# spb_sch1.net
KiCad netlist of a schematic drawn in Altium Designer
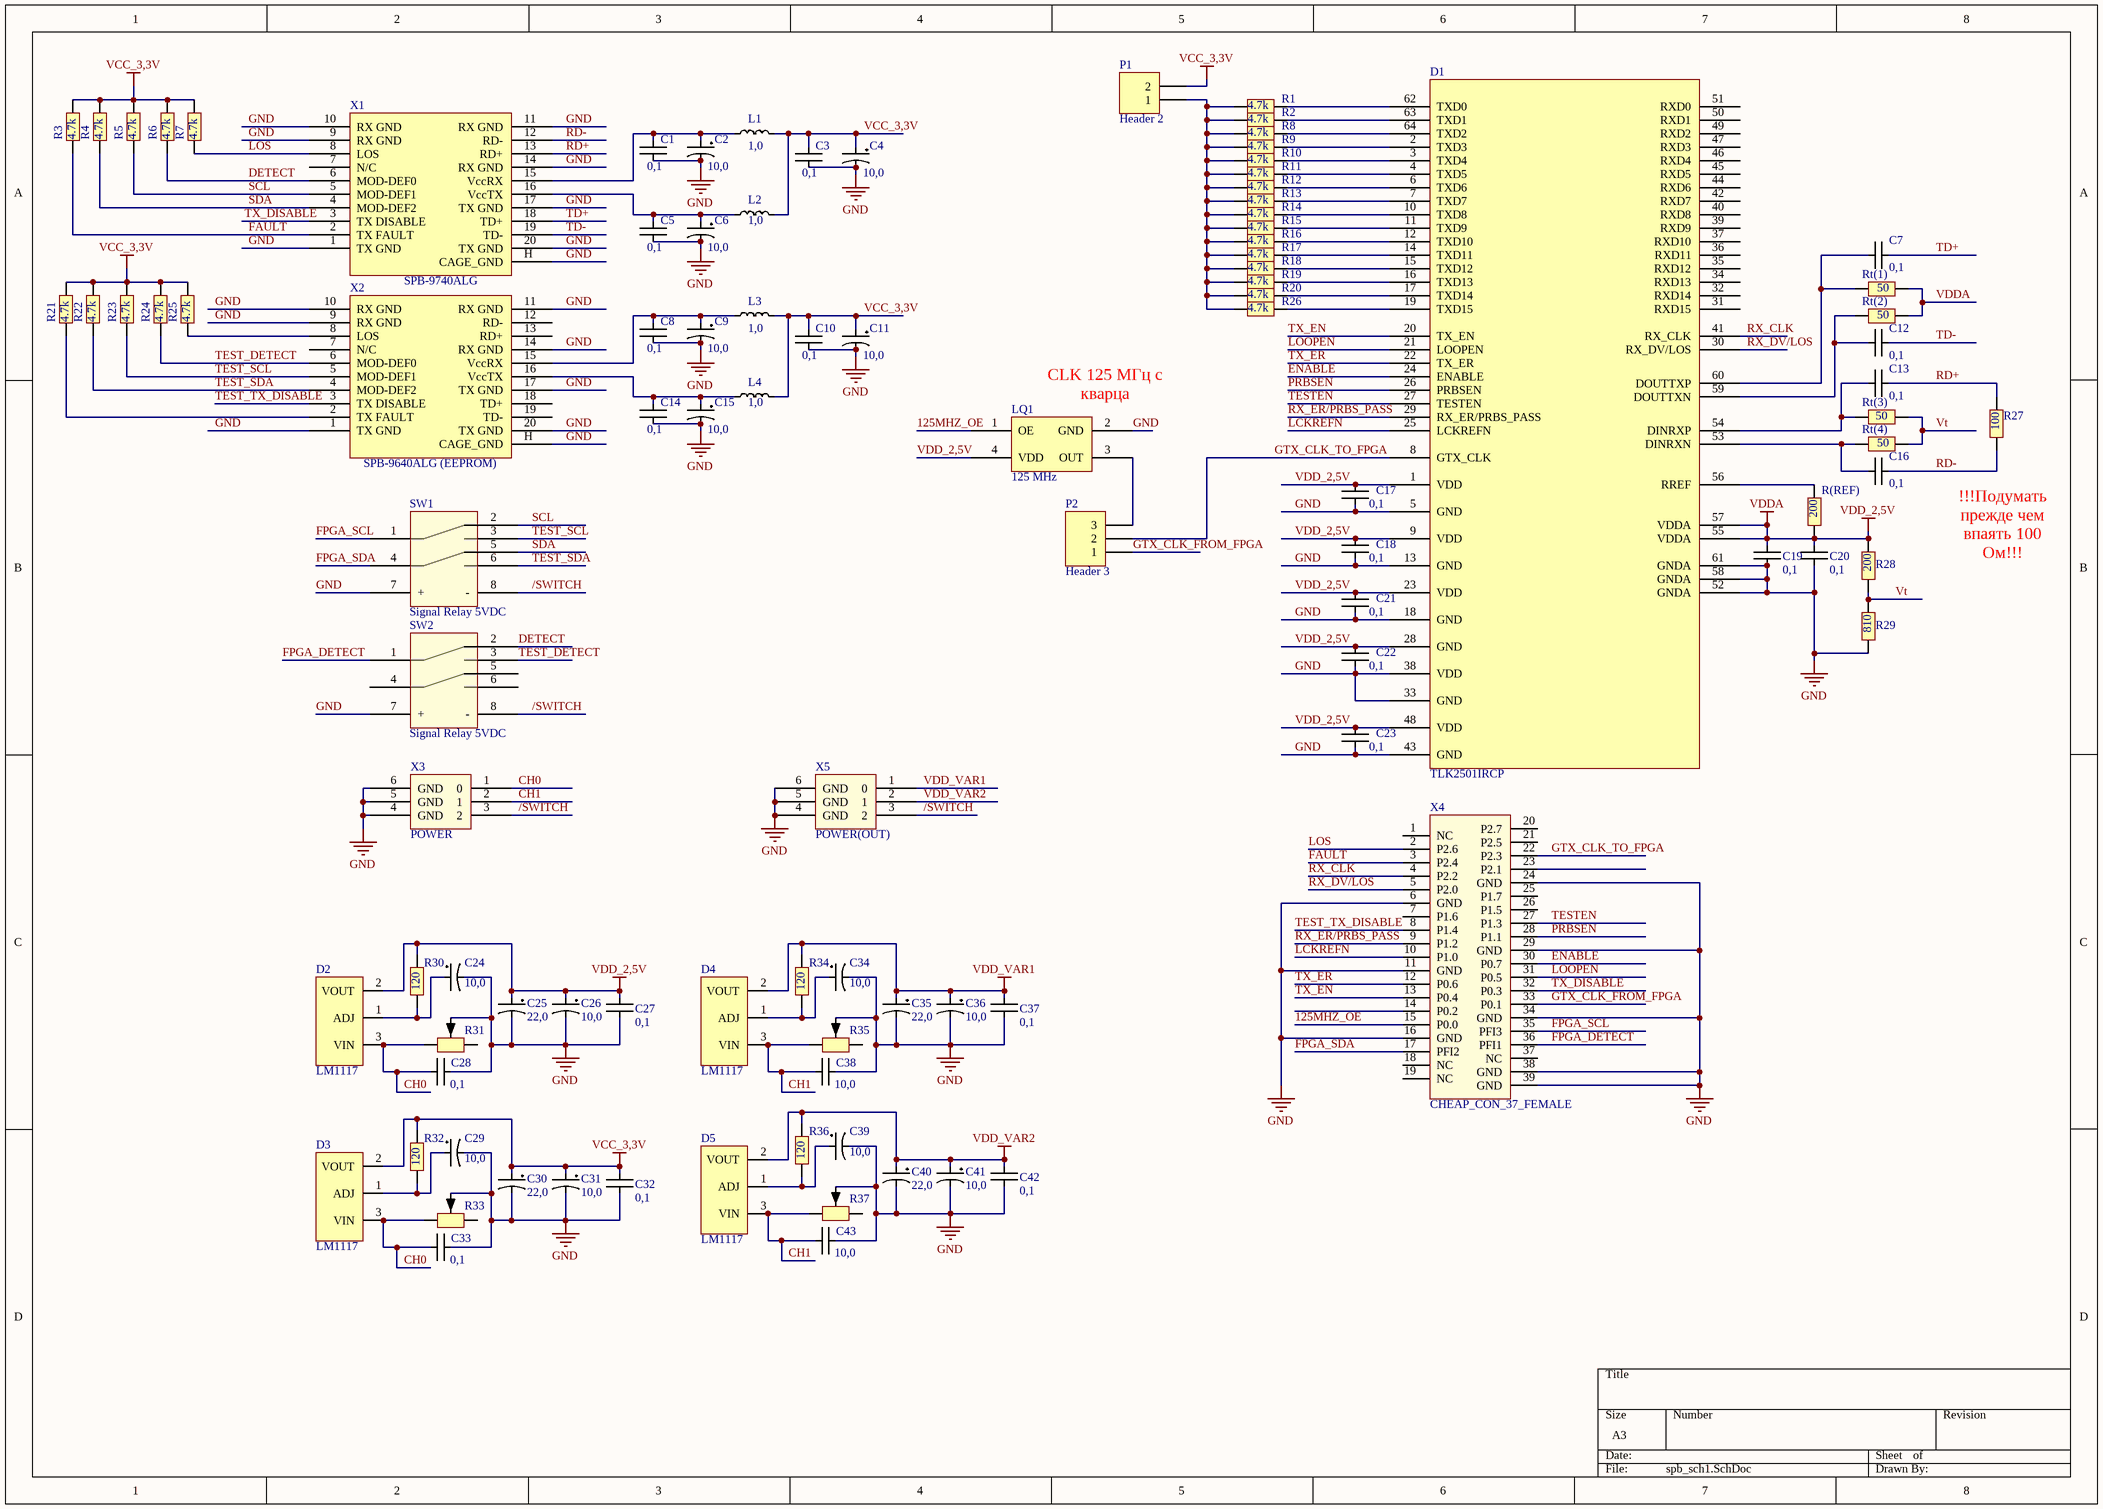
[diagram p0: spb_sch1.SchDoc]

(export (version "E")
  (design (tool "Eeschema 10.0.6"))
  (components
    (comp (ref "C1")
      (value "0,1")
      (footprint "0805")
      (description "0805")
      (libsource (lib "MIT_Schlib") (part "CAP_SMALL"))
    )
    (comp (ref "C2")
      (value "10,0")
      (footprint "TYPE_C")
      (description "SMD")
      (libsource (lib "MIT_Schlib") (part "CAP_TANT"))
    )
    (comp (ref "C3")
      (value "0,1")
      (footprint "0805")
      (description "0805")
      (libsource (lib "MIT_Schlib") (part "CAP_SMALL"))
    )
    (comp (ref "C4")
      (value "10,0")
      (footprint "TYPE_C")
      (description "SMD")
      (libsource (lib "MIT_Schlib") (part "CAP_TANT"))
    )
    (comp (ref "C5")
      (value "0,1")
      (footprint "0805")
      (description "0805")
      (libsource (lib "MIT_Schlib") (part "CAP_SMALL"))
    )
    (comp (ref "C6")
      (value "10,0")
      (footprint "TYPE_C")
      (description "SMD")
      (libsource (lib "MIT_Schlib") (part "CAP_TANT"))
    )
    (comp (ref "C7")
      (value "0,1")
      (footprint "0805")
      (description "0805")
      (libsource (lib "MIT_Schlib") (part "CAP_SMALL"))
    )
    (comp (ref "C8")
      (value "0,1")
      (footprint "0805")
      (description "0805")
      (libsource (lib "MIT_Schlib") (part "CAP_SMALL"))
    )
    (comp (ref "C9")
      (value "10,0")
      (footprint "TYPE_C")
      (description "SMD")
      (libsource (lib "MIT_Schlib") (part "CAP_TANT"))
    )
    (comp (ref "C10")
      (value "0,1")
      (footprint "0805")
      (description "0805")
      (libsource (lib "MIT_Schlib") (part "CAP_SMALL"))
    )
    (comp (ref "C11")
      (value "10,0")
      (footprint "TYPE_C")
      (description "SMD")
      (libsource (lib "MIT_Schlib") (part "CAP_TANT"))
    )
    (comp (ref "C12")
      (value "0,1")
      (footprint "0805")
      (description "0805")
      (libsource (lib "MIT_Schlib") (part "CAP_SMALL"))
    )
    (comp (ref "C13")
      (value "0,1")
      (footprint "0805")
      (description "0805")
      (libsource (lib "MIT_Schlib") (part "CAP_SMALL"))
    )
    (comp (ref "C14")
      (value "0,1")
      (footprint "0805")
      (description "0805")
      (libsource (lib "MIT_Schlib") (part "CAP_SMALL"))
    )
    (comp (ref "C15")
      (value "10,0")
      (footprint "TYPE_C")
      (description "SMD")
      (libsource (lib "MIT_Schlib") (part "CAP_TANT"))
    )
    (comp (ref "C16")
      (value "0,1")
      (footprint "0805")
      (description "0805")
      (libsource (lib "MIT_Schlib") (part "CAP_SMALL"))
    )
    (comp (ref "C17")
      (value "0,1")
      (footprint "0805")
      (description "0805")
      (libsource (lib "MIT_Schlib") (part "CAP_SMALL"))
    )
    (comp (ref "C18")
      (value "0,1")
      (footprint "0805")
      (description "0805")
      (libsource (lib "MIT_Schlib") (part "CAP_SMALL"))
    )
    (comp (ref "C19")
      (value "0,1")
      (footprint "0805")
      (description "0805")
      (libsource (lib "MIT_Schlib") (part "CAP_SMALL"))
    )
    (comp (ref "C20")
      (value "0,1")
      (footprint "0805")
      (description "0805")
      (libsource (lib "MIT_Schlib") (part "CAP_SMALL"))
    )
    (comp (ref "C21")
      (value "0,1")
      (footprint "0805")
      (description "0805")
      (libsource (lib "MIT_Schlib") (part "CAP_SMALL"))
    )
    (comp (ref "C22")
      (value "0,1")
      (footprint "0805")
      (description "0805")
      (libsource (lib "MIT_Schlib") (part "CAP_SMALL"))
    )
    (comp (ref "C23")
      (value "0,1")
      (footprint "0805")
      (description "0805")
      (libsource (lib "MIT_Schlib") (part "CAP_SMALL"))
    )
    (comp (ref "C24")
      (value "10,0")
      (footprint "TYPE_C")
      (description "SMD")
      (libsource (lib "MIT_Schlib") (part "CAP_TANT"))
    )
    (comp (ref "C25")
      (value "22,0")
      (footprint "TYPE_C")
      (description "SMD")
      (libsource (lib "MIT_Schlib") (part "CAP_TANT"))
    )
    (comp (ref "C26")
      (value "10,0")
      (footprint "TYPE_C")
      (description "SMD")
      (libsource (lib "MIT_Schlib") (part "CAP_TANT"))
    )
    (comp (ref "C27")
      (value "0,1")
      (footprint "0805")
      (description "0805")
      (libsource (lib "MIT_Schlib") (part "CAP_SMALL"))
    )
    (comp (ref "C28")
      (value "0,1")
      (footprint "0805")
      (description "0805")
      (libsource (lib "MIT_Schlib") (part "CAP_SMALL"))
    )
    (comp (ref "C29")
      (value "10,0")
      (footprint "TYPE_C")
      (description "SMD")
      (libsource (lib "MIT_Schlib") (part "CAP_TANT"))
    )
    (comp (ref "C30")
      (value "22,0")
      (footprint "TYPE_C")
      (description "SMD")
      (libsource (lib "MIT_Schlib") (part "CAP_TANT"))
    )
    (comp (ref "C31")
      (value "10,0")
      (footprint "TYPE_C")
      (description "SMD")
      (libsource (lib "MIT_Schlib") (part "CAP_TANT"))
    )
    (comp (ref "C32")
      (value "0,1")
      (footprint "0805")
      (description "0805")
      (libsource (lib "MIT_Schlib") (part "CAP_SMALL"))
    )
    (comp (ref "C33")
      (value "0,1")
      (footprint "0805")
      (description "0805")
      (libsource (lib "MIT_Schlib") (part "CAP_SMALL"))
    )
    (comp (ref "C34")
      (value "10,0")
      (footprint "TYPE_C")
      (description "SMD")
      (libsource (lib "MIT_Schlib") (part "CAP_TANT"))
    )
    (comp (ref "C35")
      (value "22,0")
      (footprint "TYPE_C")
      (description "SMD")
      (libsource (lib "MIT_Schlib") (part "CAP_TANT"))
    )
    (comp (ref "C36")
      (value "10,0")
      (footprint "TYPE_C")
      (description "SMD")
      (libsource (lib "MIT_Schlib") (part "CAP_TANT"))
    )
    (comp (ref "C37")
      (value "0,1")
      (footprint "0805")
      (description "0805")
      (libsource (lib "MIT_Schlib") (part "CAP_SMALL"))
    )
    (comp (ref "C38")
      (value "10,0")
      (footprint "0805")
      (description "0805")
      (libsource (lib "MIT_Schlib") (part "CAP_SMALL"))
    )
    (comp (ref "C39")
      (value "10,0")
      (footprint "TYPE_C")
      (description "SMD")
      (libsource (lib "MIT_Schlib") (part "CAP_TANT"))
    )
    (comp (ref "C40")
      (value "22,0")
      (footprint "TYPE_C")
      (description "SMD")
      (libsource (lib "MIT_Schlib") (part "CAP_TANT"))
    )
    (comp (ref "C41")
      (value "10,0")
      (footprint "TYPE_C")
      (description "SMD")
      (libsource (lib "MIT_Schlib") (part "CAP_TANT"))
    )
    (comp (ref "C42")
      (value "0,1")
      (footprint "0805")
      (description "0805")
      (libsource (lib "MIT_Schlib") (part "CAP_SMALL"))
    )
    (comp (ref "C43")
      (value "10,0")
      (footprint "0805")
      (description "0805")
      (libsource (lib "MIT_Schlib") (part "CAP_SMALL"))
    )
    (comp (ref "D1")
      (value "TLK2501IRCP")
      (footprint "Quad64")
      (libsource (lib "MIT_Schlib") (part "TLK2501IRCP"))
    )
    (comp (ref "D2") (value "LM1117") (footprint "TO-252") (libsource (lib "MIT_Schlib") (part "LM1117_ADJ")))
    (comp (ref "D3") (value "LM1117") (footprint "TO-252") (libsource (lib "MIT_Schlib") (part "LM1117_ADJ")))
    (comp (ref "D4") (value "LM1117") (footprint "TO-252") (libsource (lib "MIT_Schlib") (part "LM1117_ADJ")))
    (comp (ref "D5") (value "LM1117") (footprint "TO-252") (libsource (lib "MIT_Schlib") (part "LM1117_ADJ")))
    (comp (ref "L1")
      (value "1,0")
      (footprint "0805")
      (description "0805")
      (libsource (lib "MIT_Schlib") (part "INDUCT"))
    )
    (comp (ref "L2")
      (value "1,0")
      (footprint "0805")
      (description "0805")
      (libsource (lib "MIT_Schlib") (part "INDUCT"))
    )
    (comp (ref "L3")
      (value "1,0")
      (footprint "0805")
      (description "0805")
      (libsource (lib "MIT_Schlib") (part "INDUCT"))
    )
    (comp (ref "L4")
      (value "1,0")
      (footprint "0805")
      (description "0805")
      (libsource (lib "MIT_Schlib") (part "INDUCT"))
    )
    (comp (ref "LQ1")
      (value "125 MHz")
      (footprint "SOC7 SMD Clock Oscillator")
      (libsource (lib "MIT_Schlib") (part "SOC7 SMD Clock Oscillator"))
    )
    (comp (ref "P1")
      (value "Header 2")
      (footprint "HDR1X2")
      (description "Header, 2-Pin")
      (fields (field (name "PUBLISHER") "Altium Limited"))
      (libsource (lib "Miscellaneous Connectors") (part "Header 2"))
    )
    (comp (ref "P2")
      (value "Header 3")
      (footprint "HDR1X3")
      (description "Header, 3-Pin")
      (fields (field (name "PUBLISHER") "Altium Limited"))
      (libsource (lib "Miscellaneous Connectors") (part "Header 3"))
    )
    (comp (ref "R(REF)")
      (value "200")
      (footprint "0805")
      (description "0805")
      (libsource (lib "") (part "RES0805_2"))
    )
    (comp (ref "R1")
      (value "4.7k")
      (footprint "0805")
      (description "0805")
      (libsource (lib "") (part "RES0805_1"))
    )
    (comp (ref "R2")
      (value "4.7k")
      (footprint "0805")
      (description "0805")
      (libsource (lib "") (part "RES0805_1"))
    )
    (comp (ref "R3")
      (value "4.7k")
      (footprint "0805")
      (description "0805")
      (libsource (lib "") (part "RES0805_3"))
    )
    (comp (ref "R4")
      (value "4.7k")
      (footprint "0805")
      (description "0805")
      (libsource (lib "") (part "RES0805_3"))
    )
    (comp (ref "R5")
      (value "4.7k")
      (footprint "0805")
      (description "0805")
      (libsource (lib "") (part "RES0805_3"))
    )
    (comp (ref "R6")
      (value "4.7k")
      (footprint "0805")
      (description "0805")
      (libsource (lib "") (part "RES0805_3"))
    )
    (comp (ref "R7")
      (value "4.7k")
      (footprint "0805")
      (description "0805")
      (libsource (lib "") (part "RES0805_3"))
    )
    (comp (ref "R8")
      (value "4.7k")
      (footprint "0805")
      (description "0805")
      (libsource (lib "") (part "RES0805_1"))
    )
    (comp (ref "R9")
      (value "4.7k")
      (footprint "0805")
      (description "0805")
      (libsource (lib "") (part "RES0805_1"))
    )
    (comp (ref "R10")
      (value "4.7k")
      (footprint "0805")
      (description "0805")
      (libsource (lib "") (part "RES0805_1"))
    )
    (comp (ref "R11")
      (value "4.7k")
      (footprint "0805")
      (description "0805")
      (libsource (lib "") (part "RES0805_1"))
    )
    (comp (ref "R12")
      (value "4.7k")
      (footprint "0805")
      (description "0805")
      (libsource (lib "") (part "RES0805_1"))
    )
    (comp (ref "R13")
      (value "4.7k")
      (footprint "0805")
      (description "0805")
      (libsource (lib "") (part "RES0805_1"))
    )
    (comp (ref "R14")
      (value "4.7k")
      (footprint "0805")
      (description "0805")
      (libsource (lib "") (part "RES0805_1"))
    )
    (comp (ref "R15")
      (value "4.7k")
      (footprint "0805")
      (description "0805")
      (libsource (lib "") (part "RES0805_1"))
    )
    (comp (ref "R16")
      (value "4.7k")
      (footprint "0805")
      (description "0805")
      (libsource (lib "") (part "RES0805_1"))
    )
    (comp (ref "R17")
      (value "4.7k")
      (footprint "0805")
      (description "0805")
      (libsource (lib "") (part "RES0805_1"))
    )
    (comp (ref "R18")
      (value "4.7k")
      (footprint "0805")
      (description "0805")
      (libsource (lib "") (part "RES0805_1"))
    )
    (comp (ref "R19")
      (value "4.7k")
      (footprint "0805")
      (description "0805")
      (libsource (lib "") (part "RES0805_1"))
    )
    (comp (ref "R20")
      (value "4.7k")
      (footprint "0805")
      (description "0805")
      (libsource (lib "") (part "RES0805_1"))
    )
    (comp (ref "R21")
      (value "4.7k")
      (footprint "0805")
      (description "0805")
      (libsource (lib "") (part "RES0805_3"))
    )
    (comp (ref "R22")
      (value "4.7k")
      (footprint "0805")
      (description "0805")
      (libsource (lib "") (part "RES0805_3"))
    )
    (comp (ref "R23")
      (value "4.7k")
      (footprint "0805")
      (description "0805")
      (libsource (lib "") (part "RES0805_3"))
    )
    (comp (ref "R24")
      (value "4.7k")
      (footprint "0805")
      (description "0805")
      (libsource (lib "") (part "RES0805_3"))
    )
    (comp (ref "R25")
      (value "4.7k")
      (footprint "0805")
      (description "0805")
      (libsource (lib "") (part "RES0805_3"))
    )
    (comp (ref "R26")
      (value "4.7k")
      (footprint "0805")
      (description "0805")
      (libsource (lib "") (part "RES0805_1"))
    )
    (comp (ref "R27")
      (value "100")
      (footprint "0805")
      (description "0805")
      (libsource (lib "") (part "RES0805_3"))
    )
    (comp (ref "R28")
      (value "200")
      (footprint "0805")
      (description "0805")
      (libsource (lib "") (part "RES0805_2"))
    )
    (comp (ref "R29")
      (value "810")
      (footprint "0805")
      (description "0805")
      (libsource (lib "") (part "RES0805_2"))
    )
    (comp (ref "R30")
      (value "120")
      (footprint "0805")
      (description "0805")
      (libsource (lib "") (part "RES0805_3"))
    )
    (comp (ref "R31")
      (value "RES_VAR")
      (footprint "3006P")
      (description "PV36W102C (СП5-2ВБ) 1 кОм")
      (libsource (lib "MIT_Schlib") (part "RES_VAR"))
    )
    (comp (ref "R32") (value "120") (footprint "0805") (libsource (lib "") (part "RES0805_3")))
    (comp (ref "R33")
      (value "RES_VAR")
      (footprint "3006P")
      (description "PV36W102C (СП5-2ВБ) 1 кОм")
      (libsource (lib "MIT_Schlib") (part "RES_VAR"))
    )
    (comp (ref "R34")
      (value "120")
      (footprint "0805")
      (description "0805")
      (libsource (lib "") (part "RES0805_3"))
    )
    (comp (ref "R35")
      (value "RES_VAR")
      (footprint "3006P")
      (description "PV36W102C (СП5-2ВБ) 1 кОм")
      (libsource (lib "MIT_Schlib") (part "RES_VAR"))
    )
    (comp (ref "R36")
      (value "120")
      (footprint "0805")
      (description "0805")
      (libsource (lib "") (part "RES0805_3"))
    )
    (comp (ref "R37")
      (value "RES_VAR")
      (footprint "3006P")
      (description "PV36W102C (СП5-2ВБ) 1 кОм")
      (libsource (lib "MIT_Schlib") (part "RES_VAR"))
    )
    (comp (ref "Rt(1)")
      (value "50")
      (footprint "0805")
      (description "0805")
      (libsource (lib "MIT_Schlib") (part "RES0805"))
    )
    (comp (ref "Rt(2)")
      (value "50")
      (footprint "0805")
      (description "0805")
      (libsource (lib "MIT_Schlib") (part "RES0805"))
    )
    (comp (ref "Rt(3)")
      (value "50")
      (footprint "0805")
      (description "0805")
      (libsource (lib "MIT_Schlib") (part "RES0805"))
    )
    (comp (ref "Rt(4)")
      (value "50")
      (footprint "0805")
      (description "0805")
      (libsource (lib "MIT_Schlib") (part "RES0805"))
    )
    (comp (ref "SW1")
      (value "Signal Relay 5VDC")
      (footprint "V23079 Relay")
      (libsource (lib "MIT_Schlib") (part "SWITCH"))
    )
    (comp (ref "SW2")
      (value "Signal Relay 5VDC")
      (footprint "V23079 Relay")
      (libsource (lib "MIT_Schlib") (part "SWITCH"))
    )
    (comp (ref "X1")
      (value "SPB-9740ALG")
      (footprint "SFP-20pin")
      (libsource (lib "MIT_Schlib") (part "SFP-20pin"))
    )
    (comp (ref "X2")
      (value "SPB-9640ALG (EEPROM)")
      (footprint "SFP-20pin")
      (libsource (lib "MIT_Schlib") (part "SFP-20pin"))
    )
    (comp (ref "X3") (value "POWER") (footprint "POWER") (libsource (lib "Schlib") (part "POWER")))
    (comp (ref "X4")
      (value "CHEAP_CON_37_FEMALE")
      (footprint "CHEAP_CONN_FEMALE")
      (libsource (lib "Schlib") (part "CHEAP_CON_37_FEMALE"))
    )
    (comp (ref "X5") (value "POWER(OUT)") (footprint "POWER") (libsource (lib "Schlib") (part "POWER")))
  )
  (nets
    (net (code "1") (name "/125MHZ_OE") (class "Default")
      (node (ref "LQ1") (pin "1") (pinfunction "OE_1") (pintype "passive"))
      (node (ref "X4") (pin "15") (pinfunction "P0.0_15") (pintype "passive"))
    )
    (net (code "3") (name "/CH0") (class "Default")
      (node (ref "C28") (pin "1") (pinfunction "1_1") (pintype "passive"))
      (node (ref "C33") (pin "1") (pinfunction "1_1") (pintype "passive"))
      (node (ref "D2") (pin "3") (pinfunction "VIN_3") (pintype "passive"))
      (node (ref "D3") (pin "3") (pinfunction "VIN_3") (pintype "passive"))
      (node (ref "R31") (pin "3") (pinfunction "3_3") (pintype "passive"))
      (node (ref "R33") (pin "3") (pinfunction "3_3") (pintype "passive"))
      (node (ref "X3") (pin "1") (pinfunction "0_1") (pintype "passive"))
    )
    (net (code "4") (name "/CH1") (class "Default")
      (node (ref "C38") (pin "1") (pinfunction "1_1") (pintype "passive"))
      (node (ref "C43") (pin "1") (pinfunction "1_1") (pintype "passive"))
      (node (ref "D4") (pin "3") (pinfunction "VIN_3") (pintype "passive"))
      (node (ref "D5") (pin "3") (pinfunction "VIN_3") (pintype "passive"))
      (node (ref "R35") (pin "3") (pinfunction "3_3") (pintype "passive"))
      (node (ref "R37") (pin "3") (pinfunction "3_3") (pintype "passive"))
      (node (ref "X3") (pin "2") (pinfunction "1_2") (pintype "passive"))
    )
    (net (code "5") (name "/DETECT") (class "Default")
      (node (ref "R6") (pin "2") (pinfunction "2_2") (pintype "passive"))
      (node (ref "SW2") (pin "2") (pinfunction "-_2") (pintype "passive"))
      (node (ref "X1") (pin "6") (pinfunction "MOD-DEF0_6") (pintype "passive"))
    )
    (net (code "6") (name "/ENABLE") (class "Default")
      (node (ref "D1") (pin "24") (pinfunction "ENABLE_24") (pintype "passive"))
      (node (ref "X4") (pin "30") (pinfunction "P0.7_30") (pintype "passive"))
    )
    (net (code "7") (name "/FAULT") (class "Default")
      (node (ref "R3") (pin "2") (pinfunction "2_2") (pintype "passive"))
      (node (ref "X1") (pin "2") (pinfunction "TX_FAULT_2") (pintype "passive"))
      (node (ref "X4") (pin "3") (pinfunction "P2.4_3") (pintype "passive"))
    )
    (net (code "8") (name "/FPGA_DETECT") (class "Default")
      (node (ref "SW2") (pin "1") (pinfunction "-_1") (pintype "passive"))
      (node (ref "X4") (pin "36") (pinfunction "PFI1_36") (pintype "passive"))
    )
    (net (code "9") (name "/FPGA_SCL") (class "Default")
      (node (ref "SW1") (pin "1") (pinfunction "-_1") (pintype "passive"))
      (node (ref "X4") (pin "35") (pinfunction "PFI3_35") (pintype "passive"))
    )
    (net (code "10") (name "/FPGA_SDA") (class "Default")
      (node (ref "SW1") (pin "4") (pinfunction "-_4") (pintype "passive"))
      (node (ref "X4") (pin "17") (pinfunction "PFI2_17") (pintype "passive"))
    )
    (net (code "11") (name "/GTX_CLK_FROM_FPGA") (class "Default")
      (node (ref "P2") (pin "1") (pinfunction "1_1") (pintype "passive"))
      (node (ref "X4") (pin "33") (pinfunction "P0.1_33") (pintype "passive"))
    )
    (net (code "12") (name "/GTX_CLK_TO_FPGA") (class "Default")
      (node (ref "D1") (pin "8") (pinfunction "GTX_CLK_8") (pintype "passive"))
      (node (ref "P2") (pin "2") (pinfunction "2_2") (pintype "passive"))
      (node (ref "X4") (pin "22") (pinfunction "P2.3_22") (pintype "passive"))
    )
    (net (code "13") (name "/LCKREFN") (class "Default")
      (node (ref "D1") (pin "25") (pinfunction "LCKREFN_25") (pintype "passive"))
      (node (ref "X4") (pin "10") (pinfunction "P1.0_10") (pintype "passive"))
    )
    (net (code "14") (name "/LOOPEN") (class "Default")
      (node (ref "D1") (pin "21") (pinfunction "LOOPEN_21") (pintype "passive"))
      (node (ref "X4") (pin "31") (pinfunction "P0.5_31") (pintype "passive"))
    )
    (net (code "15") (name "/LOS") (class "Default")
      (node (ref "R7") (pin "2") (pinfunction "2_2") (pintype "passive"))
      (node (ref "X1") (pin "8") (pinfunction "LOS_8") (pintype "passive"))
      (node (ref "X4") (pin "2") (pinfunction "P2.6_2") (pintype "passive"))
    )
    (net (code "16") (name "/PRBSEN") (class "Default")
      (node (ref "D1") (pin "26") (pinfunction "PRBSEN_26") (pintype "passive"))
      (node (ref "X4") (pin "28") (pinfunction "P1.1_28") (pintype "passive"))
    )
    (net (code "17") (name "/RD+") (class "Default")
      (node (ref "C13") (pin "1") (pinfunction "1_1") (pintype "passive"))
      (node (ref "R27") (pin "1") (pinfunction "1_1") (pintype "passive"))
      (node (ref "X1") (pin "13") (pinfunction "RD+_13") (pintype "passive"))
    )
    (net (code "18") (name "/RD-") (class "Default")
      (node (ref "C16") (pin "1") (pinfunction "1_1") (pintype "passive"))
      (node (ref "R27") (pin "2") (pinfunction "2_2") (pintype "passive"))
      (node (ref "X1") (pin "12") (pinfunction "RD-_12") (pintype "passive"))
    )
    (net (code "19") (name "/RX_CLK") (class "Default")
      (node (ref "D1") (pin "41") (pinfunction "RX_CLK_41") (pintype "passive"))
      (node (ref "X4") (pin "4") (pinfunction "P2.2_4") (pintype "passive"))
    )
    (net (code "20") (name "/RX_DV{slash}LOS") (class "Default")
      (node (ref "D1") (pin "30") (pinfunction "RX_DV/LOS_30") (pintype "passive"))
      (node (ref "X4") (pin "5") (pinfunction "P2.0_5") (pintype "passive"))
    )
    (net (code "21") (name "/RX_ER{slash}PRBS_PASS") (class "Default")
      (node (ref "D1") (pin "29") (pinfunction "RX_ER/PRBS_PASS_29") (pintype "passive"))
      (node (ref "X4") (pin "9") (pinfunction "P1.2_9") (pintype "passive"))
    )
    (net (code "22") (name "/SCL") (class "Default")
      (node (ref "R5") (pin "2") (pinfunction "2_2") (pintype "passive"))
      (node (ref "SW1") (pin "2") (pinfunction "-_2") (pintype "passive"))
      (node (ref "X1") (pin "5") (pinfunction "MOD-DEF1_5") (pintype "passive"))
    )
    (net (code "23") (name "/SDA") (class "Default")
      (node (ref "R4") (pin "2") (pinfunction "2_2") (pintype "passive"))
      (node (ref "SW1") (pin "5") (pinfunction "-_5") (pintype "passive"))
      (node (ref "X1") (pin "4") (pinfunction "MOD-DEF2_4") (pintype "passive"))
    )
    (net (code "24") (name "/TD+") (class "Default")
      (node (ref "C7") (pin "1") (pinfunction "1_1") (pintype "passive"))
      (node (ref "X1") (pin "18") (pinfunction "TD+_18") (pintype "passive"))
    )
    (net (code "25") (name "/TD-") (class "Default")
      (node (ref "C12") (pin "1") (pinfunction "1_1") (pintype "passive"))
      (node (ref "X1") (pin "19") (pinfunction "TD-_19") (pintype "passive"))
    )
    (net (code "26") (name "/TESTEN") (class "Default")
      (node (ref "D1") (pin "27") (pinfunction "TESTEN_27") (pintype "passive"))
      (node (ref "X4") (pin "27") (pinfunction "P1.3_27") (pintype "passive"))
    )
    (net (code "27") (name "/TEST_DETECT") (class "Default")
      (node (ref "R24") (pin "2") (pinfunction "2_2") (pintype "passive"))
      (node (ref "SW2") (pin "3") (pinfunction "-_3") (pintype "passive"))
      (node (ref "X2") (pin "6") (pinfunction "MOD-DEF0_6") (pintype "passive"))
    )
    (net (code "28") (name "/TEST_SCL") (class "Default")
      (node (ref "R23") (pin "2") (pinfunction "2_2") (pintype "passive"))
      (node (ref "SW1") (pin "3") (pinfunction "-_3") (pintype "passive"))
      (node (ref "X2") (pin "5") (pinfunction "MOD-DEF1_5") (pintype "passive"))
    )
    (net (code "29") (name "/TEST_SDA") (class "Default")
      (node (ref "R22") (pin "2") (pinfunction "2_2") (pintype "passive"))
      (node (ref "SW1") (pin "6") (pinfunction "-_6") (pintype "passive"))
      (node (ref "X2") (pin "4") (pinfunction "MOD-DEF2_4") (pintype "passive"))
    )
    (net (code "30") (name "/TEST_TX_DISABLE") (class "Default")
      (node (ref "X2") (pin "3") (pinfunction "TX_DISABLE_3") (pintype "passive"))
      (node (ref "X4") (pin "8") (pinfunction "P1.4_8") (pintype "passive"))
    )
    (net (code "31") (name "/TX_DISABLE") (class "Default")
      (node (ref "X1") (pin "3") (pinfunction "TX_DISABLE_3") (pintype "passive"))
      (node (ref "X4") (pin "32") (pinfunction "P0.3_32") (pintype "passive"))
    )
    (net (code "32") (name "/TX_EN") (class "Default")
      (node (ref "D1") (pin "20") (pinfunction "TX_EN_20") (pintype "passive"))
      (node (ref "X4") (pin "13") (pinfunction "P0.4_13") (pintype "passive"))
    )
    (net (code "33") (name "/TX_ER") (class "Default")
      (node (ref "D1") (pin "22") (pinfunction "TX_ER_22") (pintype "passive"))
      (node (ref "X4") (pin "12") (pinfunction "P0.6_12") (pintype "passive"))
    )
    (net (code "34") (name "/Vt") (class "Default")
      (node (ref "R28") (pin "1") (pinfunction "1_1") (pintype "passive"))
      (node (ref "R29") (pin "2") (pinfunction "2_2") (pintype "passive"))
      (node (ref "Rt(3)") (pin "1") (pinfunction "1_1") (pintype "passive"))
      (node (ref "Rt(4)") (pin "1") (pinfunction "1_1") (pintype "passive"))
    )
    (net (code "35") (name "/{slash}SWITCH") (class "Default")
      (node (ref "SW1") (pin "8") (pinfunction "-_8") (pintype "passive"))
      (node (ref "SW2") (pin "8") (pinfunction "-_8") (pintype "passive"))
      (node (ref "X3") (pin "3") (pinfunction "2_3") (pintype "passive"))
      (node (ref "X5") (pin "3") (pinfunction "2_3") (pintype "passive"))
    )
    (net (code "36") (name "GND") (class "Default")
      (node (ref "C1") (pin "2") (pinfunction "2_2") (pintype "passive"))
      (node (ref "C10") (pin "2") (pinfunction "2_2") (pintype "passive"))
      (node (ref "C11") (pin "1") (pinfunction "1_1") (pintype "passive"))
      (node (ref "C14") (pin "2") (pinfunction "2_2") (pintype "passive"))
      (node (ref "C15") (pin "1") (pinfunction "1_1") (pintype "passive"))
      (node (ref "C17") (pin "2") (pinfunction "2_2") (pintype "passive"))
      (node (ref "C18") (pin "2") (pinfunction "2_2") (pintype "passive"))
      (node (ref "C19") (pin "1") (pinfunction "1_1") (pintype "passive"))
      (node (ref "C2") (pin "1") (pinfunction "1_1") (pintype "passive"))
      (node (ref "C20") (pin "1") (pinfunction "1_1") (pintype "passive"))
      (node (ref "C21") (pin "2") (pinfunction "2_2") (pintype "passive"))
      (node (ref "C22") (pin "2") (pinfunction "2_2") (pintype "passive"))
      (node (ref "C23") (pin "2") (pinfunction "2_2") (pintype "passive"))
      (node (ref "C24") (pin "1") (pinfunction "1_1") (pintype "passive"))
      (node (ref "C25") (pin "1") (pinfunction "1_1") (pintype "passive"))
      (node (ref "C26") (pin "1") (pinfunction "1_1") (pintype "passive"))
      (node (ref "C27") (pin "1") (pinfunction "1_1") (pintype "passive"))
      (node (ref "C28") (pin "2") (pinfunction "2_2") (pintype "passive"))
      (node (ref "C29") (pin "1") (pinfunction "1_1") (pintype "passive"))
      (node (ref "C3") (pin "2") (pinfunction "2_2") (pintype "passive"))
      (node (ref "C30") (pin "1") (pinfunction "1_1") (pintype "passive"))
      (node (ref "C31") (pin "1") (pinfunction "1_1") (pintype "passive"))
      (node (ref "C32") (pin "1") (pinfunction "1_1") (pintype "passive"))
      (node (ref "C33") (pin "2") (pinfunction "2_2") (pintype "passive"))
      (node (ref "C34") (pin "1") (pinfunction "1_1") (pintype "passive"))
      (node (ref "C35") (pin "1") (pinfunction "1_1") (pintype "passive"))
      (node (ref "C36") (pin "1") (pinfunction "1_1") (pintype "passive"))
      (node (ref "C37") (pin "1") (pinfunction "1_1") (pintype "passive"))
      (node (ref "C38") (pin "2") (pinfunction "2_2") (pintype "passive"))
      (node (ref "C39") (pin "1") (pinfunction "1_1") (pintype "passive"))
      (node (ref "C4") (pin "1") (pinfunction "1_1") (pintype "passive"))
      (node (ref "C40") (pin "1") (pinfunction "1_1") (pintype "passive"))
      (node (ref "C41") (pin "1") (pinfunction "1_1") (pintype "passive"))
      (node (ref "C42") (pin "1") (pinfunction "1_1") (pintype "passive"))
      (node (ref "C43") (pin "2") (pinfunction "2_2") (pintype "passive"))
      (node (ref "C5") (pin "2") (pinfunction "2_2") (pintype "passive"))
      (node (ref "C6") (pin "1") (pinfunction "1_1") (pintype "passive"))
      (node (ref "C8") (pin "2") (pinfunction "2_2") (pintype "passive"))
      (node (ref "C9") (pin "1") (pinfunction "1_1") (pintype "passive"))
      (node (ref "D1") (pin "13") (pinfunction "GND_13") (pintype "passive"))
      (node (ref "D1") (pin "18") (pinfunction "GND_18") (pintype "passive"))
      (node (ref "D1") (pin "33") (pinfunction "GND_33") (pintype "passive"))
      (node (ref "D1") (pin "38") (pinfunction "VDD_38") (pintype "passive"))
      (node (ref "D1") (pin "43") (pinfunction "GND_43") (pintype "passive"))
      (node (ref "D1") (pin "5") (pinfunction "GND_5") (pintype "passive"))
      (node (ref "D1") (pin "52") (pinfunction "GNDA_52") (pintype "passive"))
      (node (ref "D1") (pin "58") (pinfunction "GNDA_58") (pintype "passive"))
      (node (ref "D1") (pin "61") (pinfunction "GNDA_61") (pintype "passive"))
      (node (ref "LQ1") (pin "2") (pinfunction "GND_2") (pintype "passive"))
      (node (ref "R29") (pin "1") (pinfunction "1_1") (pintype "passive"))
      (node (ref "R31") (pin "2") (pinfunction "2_2") (pintype "passive"))
      (node (ref "R33") (pin "2") (pinfunction "2_2") (pintype "passive"))
      (node (ref "R35") (pin "2") (pinfunction "2_2") (pintype "passive"))
      (node (ref "R37") (pin "2") (pinfunction "2_2") (pintype "passive"))
      (node (ref "SW1") (pin "7") (pinfunction "+_7") (pintype "passive"))
      (node (ref "SW2") (pin "7") (pinfunction "+_7") (pintype "passive"))
      (node (ref "X1") (pin "1") (pinfunction "TX_GND_1") (pintype "passive"))
      (node (ref "X1") (pin "10") (pinfunction "RX_GND_10") (pintype "passive"))
      (node (ref "X1") (pin "11") (pinfunction "RX_GND_11") (pintype "passive"))
      (node (ref "X1") (pin "14") (pinfunction "RX_GND_14") (pintype "passive"))
      (node (ref "X1") (pin "17") (pinfunction "TX_GND_17") (pintype "passive"))
      (node (ref "X1") (pin "20") (pinfunction "TX_GND_20") (pintype "passive"))
      (node (ref "X1") (pin "9") (pinfunction "RX_GND_9") (pintype "passive"))
      (node (ref "X1") (pin "H") (pinfunction "CAGE_GND_H") (pintype "passive"))
      (node (ref "X2") (pin "1") (pinfunction "TX_GND_1") (pintype "passive"))
      (node (ref "X2") (pin "10") (pinfunction "RX_GND_10") (pintype "passive"))
      (node (ref "X2") (pin "11") (pinfunction "RX_GND_11") (pintype "passive"))
      (node (ref "X2") (pin "14") (pinfunction "RX_GND_14") (pintype "passive"))
      (node (ref "X2") (pin "17") (pinfunction "TX_GND_17") (pintype "passive"))
      (node (ref "X2") (pin "20") (pinfunction "TX_GND_20") (pintype "passive"))
      (node (ref "X2") (pin "9") (pinfunction "RX_GND_9") (pintype "passive"))
      (node (ref "X2") (pin "H") (pinfunction "CAGE_GND_H") (pintype "passive"))
      (node (ref "X3") (pin "4") (pinfunction "GND_4") (pintype "passive"))
      (node (ref "X3") (pin "5") (pinfunction "GND_5") (pintype "passive"))
      (node (ref "X3") (pin "6") (pinfunction "GND_6") (pintype "passive"))
      (node (ref "X4") (pin "11") (pinfunction "GND_11") (pintype "passive"))
      (node (ref "X4") (pin "16") (pinfunction "GND_16") (pintype "passive"))
      (node (ref "X4") (pin "24") (pinfunction "GND_24") (pintype "passive"))
      (node (ref "X4") (pin "29") (pinfunction "GND_29") (pintype "passive"))
      (node (ref "X4") (pin "34") (pinfunction "GND_34") (pintype "passive"))
      (node (ref "X4") (pin "38") (pinfunction "GND_38") (pintype "passive"))
      (node (ref "X4") (pin "39") (pinfunction "GND_39") (pintype "passive"))
      (node (ref "X4") (pin "6") (pinfunction "GND_6") (pintype "passive"))
      (node (ref "X5") (pin "4") (pinfunction "GND_4") (pintype "passive"))
      (node (ref "X5") (pin "5") (pinfunction "GND_5") (pintype "passive"))
      (node (ref "X5") (pin "6") (pinfunction "GND_6") (pintype "passive"))
    )
    (net (code "37") (name "Net-(D1-DINRXN)") (class "Default")
      (node (ref "C16") (pin "2") (pinfunction "2_2") (pintype "passive"))
      (node (ref "D1") (pin "53") (pinfunction "DINRXN_53") (pintype "passive"))
      (node (ref "Rt(4)") (pin "2") (pinfunction "2_2") (pintype "passive"))
    )
    (net (code "38") (name "Net-(D1-DINRXP)") (class "Default")
      (node (ref "C13") (pin "2") (pinfunction "2_2") (pintype "passive"))
      (node (ref "D1") (pin "54") (pinfunction "DINRXP_54") (pintype "passive"))
      (node (ref "Rt(3)") (pin "2") (pinfunction "2_2") (pintype "passive"))
    )
    (net (code "39") (name "Net-(D1-DOUTTXN)") (class "Default")
      (node (ref "C12") (pin "2") (pinfunction "2_2") (pintype "passive"))
      (node (ref "D1") (pin "59") (pinfunction "DOUTTXN_59") (pintype "passive"))
      (node (ref "Rt(2)") (pin "2") (pinfunction "2_2") (pintype "passive"))
    )
    (net (code "40") (name "Net-(D1-DOUTTXP)") (class "Default")
      (node (ref "C7") (pin "2") (pinfunction "2_2") (pintype "passive"))
      (node (ref "D1") (pin "60") (pinfunction "DOUTTXP_60") (pintype "passive"))
      (node (ref "Rt(1)") (pin "2") (pinfunction "2_2") (pintype "passive"))
    )
    (net (code "41") (name "Net-(D1-RREF)") (class "Default")
      (node (ref "D1") (pin "56") (pinfunction "RREF_56") (pintype "passive"))
      (node (ref "R(REF)") (pin "2") (pinfunction "2_2") (pintype "passive"))
    )
    (net (code "42") (name "Net-(D1-TXD0)") (class "Default")
      (node (ref "D1") (pin "62") (pinfunction "TXD0_62") (pintype "passive"))
      (node (ref "R1") (pin "2") (pinfunction "2_2") (pintype "passive"))
    )
    (net (code "43") (name "Net-(D1-TXD1)") (class "Default")
      (node (ref "D1") (pin "63") (pinfunction "TXD1_63") (pintype "passive"))
      (node (ref "R2") (pin "2") (pinfunction "2_2") (pintype "passive"))
    )
    (net (code "44") (name "Net-(D1-TXD2)") (class "Default")
      (node (ref "D1") (pin "64") (pinfunction "TXD2_64") (pintype "passive"))
      (node (ref "R8") (pin "2") (pinfunction "2_2") (pintype "passive"))
    )
    (net (code "45") (name "Net-(D1-TXD3)") (class "Default")
      (node (ref "D1") (pin "2") (pinfunction "TXD3_2") (pintype "passive"))
      (node (ref "R9") (pin "2") (pinfunction "2_2") (pintype "passive"))
    )
    (net (code "46") (name "Net-(D1-TXD4)") (class "Default")
      (node (ref "D1") (pin "3") (pinfunction "TXD4_3") (pintype "passive"))
      (node (ref "R10") (pin "2") (pinfunction "2_2") (pintype "passive"))
    )
    (net (code "47") (name "Net-(D1-TXD5)") (class "Default")
      (node (ref "D1") (pin "4") (pinfunction "TXD5_4") (pintype "passive"))
      (node (ref "R11") (pin "2") (pinfunction "2_2") (pintype "passive"))
    )
    (net (code "48") (name "Net-(D1-TXD6)") (class "Default")
      (node (ref "D1") (pin "6") (pinfunction "TXD6_6") (pintype "passive"))
      (node (ref "R12") (pin "2") (pinfunction "2_2") (pintype "passive"))
    )
    (net (code "49") (name "Net-(D1-TXD7)") (class "Default")
      (node (ref "D1") (pin "7") (pinfunction "TXD7_7") (pintype "passive"))
      (node (ref "R13") (pin "2") (pinfunction "2_2") (pintype "passive"))
    )
    (net (code "50") (name "Net-(D1-TXD8)") (class "Default")
      (node (ref "D1") (pin "10") (pinfunction "TXD8_10") (pintype "passive"))
      (node (ref "R14") (pin "2") (pinfunction "2_2") (pintype "passive"))
    )
    (net (code "51") (name "Net-(D1-TXD9)") (class "Default")
      (node (ref "D1") (pin "11") (pinfunction "TXD9_11") (pintype "passive"))
      (node (ref "R15") (pin "2") (pinfunction "2_2") (pintype "passive"))
    )
    (net (code "52") (name "Net-(D1-TXD10)") (class "Default")
      (node (ref "D1") (pin "12") (pinfunction "TXD10_12") (pintype "passive"))
      (node (ref "R16") (pin "2") (pinfunction "2_2") (pintype "passive"))
    )
    (net (code "53") (name "Net-(D1-TXD11)") (class "Default")
      (node (ref "D1") (pin "14") (pinfunction "TXD11_14") (pintype "passive"))
      (node (ref "R17") (pin "2") (pinfunction "2_2") (pintype "passive"))
    )
    (net (code "54") (name "Net-(D1-TXD12)") (class "Default")
      (node (ref "D1") (pin "15") (pinfunction "TXD12_15") (pintype "passive"))
      (node (ref "R18") (pin "2") (pinfunction "2_2") (pintype "passive"))
    )
    (net (code "55") (name "Net-(D1-TXD13)") (class "Default")
      (node (ref "D1") (pin "16") (pinfunction "TXD13_16") (pintype "passive"))
      (node (ref "R19") (pin "2") (pinfunction "2_2") (pintype "passive"))
    )
    (net (code "56") (name "Net-(D1-TXD14)") (class "Default")
      (node (ref "D1") (pin "17") (pinfunction "TXD14_17") (pintype "passive"))
      (node (ref "R20") (pin "2") (pinfunction "2_2") (pintype "passive"))
    )
    (net (code "57") (name "Net-(D1-TXD15)") (class "Default")
      (node (ref "D1") (pin "19") (pinfunction "TXD15_19") (pintype "passive"))
      (node (ref "R26") (pin "2") (pinfunction "2_2") (pintype "passive"))
    )
    (net (code "58") (name "Net-(D2-ADJ)") (class "Default")
      (node (ref "C24") (pin "2") (pinfunction "2_2") (pintype "passive"))
      (node (ref "D2") (pin "1") (pinfunction "ADJ_1") (pintype "passive"))
      (node (ref "R30") (pin "2") (pinfunction "2_2") (pintype "passive"))
    )
    (net (code "59") (name "Net-(D3-ADJ)") (class "Default")
      (node (ref "C29") (pin "2") (pinfunction "2_2") (pintype "passive"))
      (node (ref "D3") (pin "1") (pinfunction "ADJ_1") (pintype "passive"))
      (node (ref "R32") (pin "2") (pinfunction "2_2") (pintype "passive"))
    )
    (net (code "60") (name "Net-(D4-ADJ)") (class "Default")
      (node (ref "C34") (pin "2") (pinfunction "2_2") (pintype "passive"))
      (node (ref "D4") (pin "1") (pinfunction "ADJ_1") (pintype "passive"))
      (node (ref "R34") (pin "2") (pinfunction "2_2") (pintype "passive"))
    )
    (net (code "61") (name "Net-(D5-ADJ)") (class "Default")
      (node (ref "C39") (pin "2") (pinfunction "2_2") (pintype "passive"))
      (node (ref "D5") (pin "1") (pinfunction "ADJ_1") (pintype "passive"))
      (node (ref "R36") (pin "2") (pinfunction "2_2") (pintype "passive"))
    )
    (net (code "62") (name "Net-(LQ1-OUT)") (class "Default")
      (node (ref "LQ1") (pin "3") (pinfunction "OUT_3") (pintype "passive"))
      (node (ref "P2") (pin "3") (pinfunction "3_3") (pintype "passive"))
    )
    (net (code "63") (name "Net-(P1-Pad1)") (class "Default")
      (node (ref "P1") (pin "1") (pinfunction "1_1") (pintype "passive"))
      (node (ref "R1") (pin "1") (pinfunction "1_1") (pintype "passive"))
      (node (ref "R10") (pin "1") (pinfunction "1_1") (pintype "passive"))
      (node (ref "R11") (pin "1") (pinfunction "1_1") (pintype "passive"))
      (node (ref "R12") (pin "1") (pinfunction "1_1") (pintype "passive"))
      (node (ref "R13") (pin "1") (pinfunction "1_1") (pintype "passive"))
      (node (ref "R14") (pin "1") (pinfunction "1_1") (pintype "passive"))
      (node (ref "R15") (pin "1") (pinfunction "1_1") (pintype "passive"))
      (node (ref "R16") (pin "1") (pinfunction "1_1") (pintype "passive"))
      (node (ref "R17") (pin "1") (pinfunction "1_1") (pintype "passive"))
      (node (ref "R18") (pin "1") (pinfunction "1_1") (pintype "passive"))
      (node (ref "R19") (pin "1") (pinfunction "1_1") (pintype "passive"))
      (node (ref "R2") (pin "1") (pinfunction "1_1") (pintype "passive"))
      (node (ref "R20") (pin "1") (pinfunction "1_1") (pintype "passive"))
      (node (ref "R26") (pin "1") (pinfunction "1_1") (pintype "passive"))
      (node (ref "R8") (pin "1") (pinfunction "1_1") (pintype "passive"))
      (node (ref "R9") (pin "1") (pinfunction "1_1") (pintype "passive"))
    )
    (net (code "64") (name "Net-(X1-VccRX)") (class "Default")
      (node (ref "C1") (pin "1") (pinfunction "1_1") (pintype "passive"))
      (node (ref "C2") (pin "2") (pinfunction "2_2") (pintype "passive"))
      (node (ref "L1") (pin "1") (pinfunction "1_1") (pintype "passive"))
      (node (ref "X1") (pin "15") (pinfunction "VccRX_15") (pintype "passive"))
    )
    (net (code "65") (name "Net-(X1-VccTX)") (class "Default")
      (node (ref "C5") (pin "1") (pinfunction "1_1") (pintype "passive"))
      (node (ref "C6") (pin "2") (pinfunction "2_2") (pintype "passive"))
      (node (ref "L2") (pin "1") (pinfunction "1_1") (pintype "passive"))
      (node (ref "X1") (pin "16") (pinfunction "VccTX_16") (pintype "passive"))
    )
    (net (code "66") (name "Net-(X2-LOS)") (class "Default")
      (node (ref "R25") (pin "2") (pinfunction "2_2") (pintype "passive"))
      (node (ref "X2") (pin "8") (pinfunction "LOS_8") (pintype "passive"))
    )
    (net (code "67") (name "Net-(X2-TX_FAULT)") (class "Default")
      (node (ref "R21") (pin "2") (pinfunction "2_2") (pintype "passive"))
      (node (ref "X2") (pin "2") (pinfunction "TX_FAULT_2") (pintype "passive"))
    )
    (net (code "68") (name "Net-(X2-VccRX)") (class "Default")
      (node (ref "C8") (pin "1") (pinfunction "1_1") (pintype "passive"))
      (node (ref "C9") (pin "2") (pinfunction "2_2") (pintype "passive"))
      (node (ref "L3") (pin "1") (pinfunction "1_1") (pintype "passive"))
      (node (ref "X2") (pin "15") (pinfunction "VccRX_15") (pintype "passive"))
    )
    (net (code "69") (name "Net-(X2-VccTX)") (class "Default")
      (node (ref "C14") (pin "1") (pinfunction "1_1") (pintype "passive"))
      (node (ref "C15") (pin "2") (pinfunction "2_2") (pintype "passive"))
      (node (ref "L4") (pin "1") (pinfunction "1_1") (pintype "passive"))
      (node (ref "X2") (pin "16") (pinfunction "VccTX_16") (pintype "passive"))
    )
    (net (code "70") (name "VCC_3,3V") (class "Default")
      (node (ref "C10") (pin "1") (pinfunction "1_1") (pintype "passive"))
      (node (ref "C11") (pin "2") (pinfunction "2_2") (pintype "passive"))
      (node (ref "C3") (pin "1") (pinfunction "1_1") (pintype "passive"))
      (node (ref "C30") (pin "2") (pinfunction "2_2") (pintype "passive"))
      (node (ref "C31") (pin "2") (pinfunction "2_2") (pintype "passive"))
      (node (ref "C32") (pin "2") (pinfunction "2_2") (pintype "passive"))
      (node (ref "C4") (pin "2") (pinfunction "2_2") (pintype "passive"))
      (node (ref "D3") (pin "2") (pinfunction "VOUT_2") (pintype "passive"))
      (node (ref "L1") (pin "2") (pinfunction "2_2") (pintype "passive"))
      (node (ref "L2") (pin "2") (pinfunction "2_2") (pintype "passive"))
      (node (ref "L3") (pin "2") (pinfunction "2_2") (pintype "passive"))
      (node (ref "L4") (pin "2") (pinfunction "2_2") (pintype "passive"))
      (node (ref "P1") (pin "2") (pinfunction "2_2") (pintype "passive"))
      (node (ref "R21") (pin "1") (pinfunction "1_1") (pintype "passive"))
      (node (ref "R22") (pin "1") (pinfunction "1_1") (pintype "passive"))
      (node (ref "R23") (pin "1") (pinfunction "1_1") (pintype "passive"))
      (node (ref "R24") (pin "1") (pinfunction "1_1") (pintype "passive"))
      (node (ref "R25") (pin "1") (pinfunction "1_1") (pintype "passive"))
      (node (ref "R3") (pin "1") (pinfunction "1_1") (pintype "passive"))
      (node (ref "R32") (pin "1") (pinfunction "1_1") (pintype "passive"))
      (node (ref "R4") (pin "1") (pinfunction "1_1") (pintype "passive"))
      (node (ref "R5") (pin "1") (pinfunction "1_1") (pintype "passive"))
      (node (ref "R6") (pin "1") (pinfunction "1_1") (pintype "passive"))
      (node (ref "R7") (pin "1") (pinfunction "1_1") (pintype "passive"))
    )
    (net (code "71") (name "VDDA") (class "Default")
      (node (ref "C17") (pin "1") (pinfunction "1_1") (pintype "passive"))
      (node (ref "C18") (pin "1") (pinfunction "1_1") (pintype "passive"))
      (node (ref "C19") (pin "2") (pinfunction "2_2") (pintype "passive"))
      (node (ref "C20") (pin "2") (pinfunction "2_2") (pintype "passive"))
      (node (ref "C21") (pin "1") (pinfunction "1_1") (pintype "passive"))
      (node (ref "C22") (pin "1") (pinfunction "1_1") (pintype "passive"))
      (node (ref "C23") (pin "1") (pinfunction "1_1") (pintype "passive"))
      (node (ref "C25") (pin "2") (pinfunction "2_2") (pintype "passive"))
      (node (ref "C26") (pin "2") (pinfunction "2_2") (pintype "passive"))
      (node (ref "C27") (pin "2") (pinfunction "2_2") (pintype "passive"))
      (node (ref "D1") (pin "1") (pinfunction "VDD_1") (pintype "passive"))
      (node (ref "D1") (pin "23") (pinfunction "VDD_23") (pintype "passive"))
      (node (ref "D1") (pin "28") (pinfunction "GND_28") (pintype "passive"))
      (node (ref "D1") (pin "48") (pinfunction "VDD_48") (pintype "passive"))
      (node (ref "D1") (pin "55") (pinfunction "VDDA_55") (pintype "passive"))
      (node (ref "D1") (pin "57") (pinfunction "VDDA_57") (pintype "passive"))
      (node (ref "D1") (pin "9") (pinfunction "VDD_9") (pintype "passive"))
      (node (ref "D2") (pin "2") (pinfunction "VOUT_2") (pintype "passive"))
      (node (ref "LQ1") (pin "4") (pinfunction "VDD_4") (pintype "passive"))
      (node (ref "R(REF)") (pin "1") (pinfunction "1_1") (pintype "passive"))
      (node (ref "R28") (pin "2") (pinfunction "2_2") (pintype "passive"))
      (node (ref "R30") (pin "1") (pinfunction "1_1") (pintype "passive"))
      (node (ref "Rt(1)") (pin "1") (pinfunction "1_1") (pintype "passive"))
      (node (ref "Rt(2)") (pin "1") (pinfunction "1_1") (pintype "passive"))
    )
    (net (code "72") (name "VDD_VAR1") (class "Default")
      (node (ref "C35") (pin "2") (pinfunction "2_2") (pintype "passive"))
      (node (ref "C36") (pin "2") (pinfunction "2_2") (pintype "passive"))
      (node (ref "C37") (pin "2") (pinfunction "2_2") (pintype "passive"))
      (node (ref "D4") (pin "2") (pinfunction "VOUT_2") (pintype "passive"))
      (node (ref "R34") (pin "1") (pinfunction "1_1") (pintype "passive"))
      (node (ref "X5") (pin "1") (pinfunction "0_1") (pintype "passive"))
    )
    (net (code "73") (name "VDD_VAR2") (class "Default")
      (node (ref "C40") (pin "2") (pinfunction "2_2") (pintype "passive"))
      (node (ref "C41") (pin "2") (pinfunction "2_2") (pintype "passive"))
      (node (ref "C42") (pin "2") (pinfunction "2_2") (pintype "passive"))
      (node (ref "D5") (pin "2") (pinfunction "VOUT_2") (pintype "passive"))
      (node (ref "R36") (pin "1") (pinfunction "1_1") (pintype "passive"))
      (node (ref "X5") (pin "2") (pinfunction "1_2") (pintype "passive"))
    )
    (net (code "74") (name "unconnected-(D1-RXD0-Pad51)") (class "Default")
      (node (ref "D1") (pin "51") (pinfunction "RXD0_51") (pintype "passive"))
    )
    (net (code "75") (name "unconnected-(D1-RXD1-Pad50)") (class "Default")
      (node (ref "D1") (pin "50") (pinfunction "RXD1_50") (pintype "passive"))
    )
    (net (code "76") (name "unconnected-(D1-RXD2-Pad49)") (class "Default")
      (node (ref "D1") (pin "49") (pinfunction "RXD2_49") (pintype "passive"))
    )
    (net (code "77") (name "unconnected-(D1-RXD3-Pad47)") (class "Default")
      (node (ref "D1") (pin "47") (pinfunction "RXD3_47") (pintype "passive"))
    )
    (net (code "78") (name "unconnected-(D1-RXD4-Pad46)") (class "Default")
      (node (ref "D1") (pin "46") (pinfunction "RXD4_46") (pintype "passive"))
    )
    (net (code "79") (name "unconnected-(D1-RXD5-Pad45)") (class "Default")
      (node (ref "D1") (pin "45") (pinfunction "RXD5_45") (pintype "passive"))
    )
    (net (code "80") (name "unconnected-(D1-RXD6-Pad44)") (class "Default")
      (node (ref "D1") (pin "44") (pinfunction "RXD6_44") (pintype "passive"))
    )
    (net (code "81") (name "unconnected-(D1-RXD7-Pad42)") (class "Default")
      (node (ref "D1") (pin "42") (pinfunction "RXD7_42") (pintype "passive"))
    )
    (net (code "82") (name "unconnected-(D1-RXD8-Pad40)") (class "Default")
      (node (ref "D1") (pin "40") (pinfunction "RXD8_40") (pintype "passive"))
    )
    (net (code "83") (name "unconnected-(D1-RXD9-Pad39)") (class "Default")
      (node (ref "D1") (pin "39") (pinfunction "RXD9_39") (pintype "passive"))
    )
    (net (code "84") (name "unconnected-(D1-RXD10-Pad37)") (class "Default")
      (node (ref "D1") (pin "37") (pinfunction "RXD10_37") (pintype "passive"))
    )
    (net (code "85") (name "unconnected-(D1-RXD11-Pad36)") (class "Default")
      (node (ref "D1") (pin "36") (pinfunction "RXD11_36") (pintype "passive"))
    )
    (net (code "86") (name "unconnected-(D1-RXD12-Pad35)") (class "Default")
      (node (ref "D1") (pin "35") (pinfunction "RXD12_35") (pintype "passive"))
    )
    (net (code "87") (name "unconnected-(D1-RXD13-Pad34)") (class "Default")
      (node (ref "D1") (pin "34") (pinfunction "RXD13_34") (pintype "passive"))
    )
    (net (code "88") (name "unconnected-(D1-RXD14-Pad32)") (class "Default")
      (node (ref "D1") (pin "32") (pinfunction "RXD14_32") (pintype "passive"))
    )
    (net (code "89") (name "unconnected-(D1-RXD15-Pad31)") (class "Default")
      (node (ref "D1") (pin "31") (pinfunction "RXD15_31") (pintype "passive"))
    )
    (net (code "90") (name "unconnected-(R31-Pad1)") (class "Default")
      (node (ref "R31") (pin "1") (pinfunction "1_1") (pintype "passive"))
    )
    (net (code "91") (name "unconnected-(R33-Pad1)") (class "Default")
      (node (ref "R33") (pin "1") (pinfunction "1_1") (pintype "passive"))
    )
    (net (code "92") (name "unconnected-(R35-Pad1)") (class "Default")
      (node (ref "R35") (pin "1") (pinfunction "1_1") (pintype "passive"))
    )
    (net (code "93") (name "unconnected-(R37-Pad1)") (class "Default")
      (node (ref "R37") (pin "1") (pinfunction "1_1") (pintype "passive"))
    )
    (net (code "94") (name "unconnected-(SW2---Pad4)") (class "Default")
      (node (ref "SW2") (pin "4") (pinfunction "-_4") (pintype "passive"))
    )
    (net (code "95") (name "unconnected-(SW2---Pad5)") (class "Default")
      (node (ref "SW2") (pin "5") (pinfunction "-_5") (pintype "passive"))
    )
    (net (code "96") (name "unconnected-(SW2---Pad6)") (class "Default")
      (node (ref "SW2") (pin "6") (pinfunction "-_6") (pintype "passive"))
    )
    (net (code "97") (name "unconnected-(X1-N{slash}C-Pad7)") (class "Default")
      (node (ref "X1") (pin "7") (pinfunction "N/C_7") (pintype "passive"))
    )
    (net (code "98") (name "unconnected-(X2-N{slash}C-Pad7)") (class "Default")
      (node (ref "X2") (pin "7") (pinfunction "N/C_7") (pintype "passive"))
    )
    (net (code "99") (name "unconnected-(X2-RD+-Pad13)") (class "Default")
      (node (ref "X2") (pin "13") (pinfunction "RD+_13") (pintype "passive"))
    )
    (net (code "100") (name "unconnected-(X2-RD--Pad12)") (class "Default")
      (node (ref "X2") (pin "12") (pinfunction "RD-_12") (pintype "passive"))
    )
    (net (code "101") (name "unconnected-(X2-TD+-Pad18)") (class "Default")
      (node (ref "X2") (pin "18") (pinfunction "TD+_18") (pintype "passive"))
    )
    (net (code "102") (name "unconnected-(X2-TD--Pad19)") (class "Default")
      (node (ref "X2") (pin "19") (pinfunction "TD-_19") (pintype "passive"))
    )
    (net (code "103") (name "unconnected-(X4-NC-Pad1)") (class "Default")
      (node (ref "X4") (pin "1") (pinfunction "NC_1") (pintype "passive"))
    )
    (net (code "104") (name "unconnected-(X4-NC-Pad18)") (class "Default")
      (node (ref "X4") (pin "18") (pinfunction "NC_18") (pintype "passive"))
    )
    (net (code "105") (name "unconnected-(X4-NC-Pad19)") (class "Default")
      (node (ref "X4") (pin "19") (pinfunction "NC_19") (pintype "passive"))
    )
    (net (code "106") (name "unconnected-(X4-NC-Pad37)") (class "Default")
      (node (ref "X4") (pin "37") (pinfunction "NC_37") (pintype "passive"))
    )
    (net (code "107") (name "unconnected-(X4-P0.2-Pad14)") (class "Default")
      (node (ref "X4") (pin "14") (pinfunction "P0.2_14") (pintype "passive"))
    )
    (net (code "108") (name "unconnected-(X4-P1.5-Pad26)") (class "Default")
      (node (ref "X4") (pin "26") (pinfunction "P1.5_26") (pintype "passive"))
    )
    (net (code "109") (name "unconnected-(X4-P1.6-Pad7)") (class "Default")
      (node (ref "X4") (pin "7") (pinfunction "P1.6_7") (pintype "passive"))
    )
    (net (code "110") (name "unconnected-(X4-P1.7-Pad25)") (class "Default")
      (node (ref "X4") (pin "25") (pinfunction "P1.7_25") (pintype "passive"))
    )
    (net (code "111") (name "unconnected-(X4-P2.1-Pad23)") (class "Default")
      (node (ref "X4") (pin "23") (pinfunction "P2.1_23") (pintype "passive"))
    )
    (net (code "112") (name "unconnected-(X4-P2.5-Pad21)") (class "Default")
      (node (ref "X4") (pin "21") (pinfunction "P2.5_21") (pintype "passive"))
    )
    (net (code "113") (name "unconnected-(X4-P2.7-Pad20)") (class "Default")
      (node (ref "X4") (pin "20") (pinfunction "P2.7_20") (pintype "passive"))
    )
  )
)
